# scout_mk2.net
KiCad netlist of a schematic drawn in EAGLE
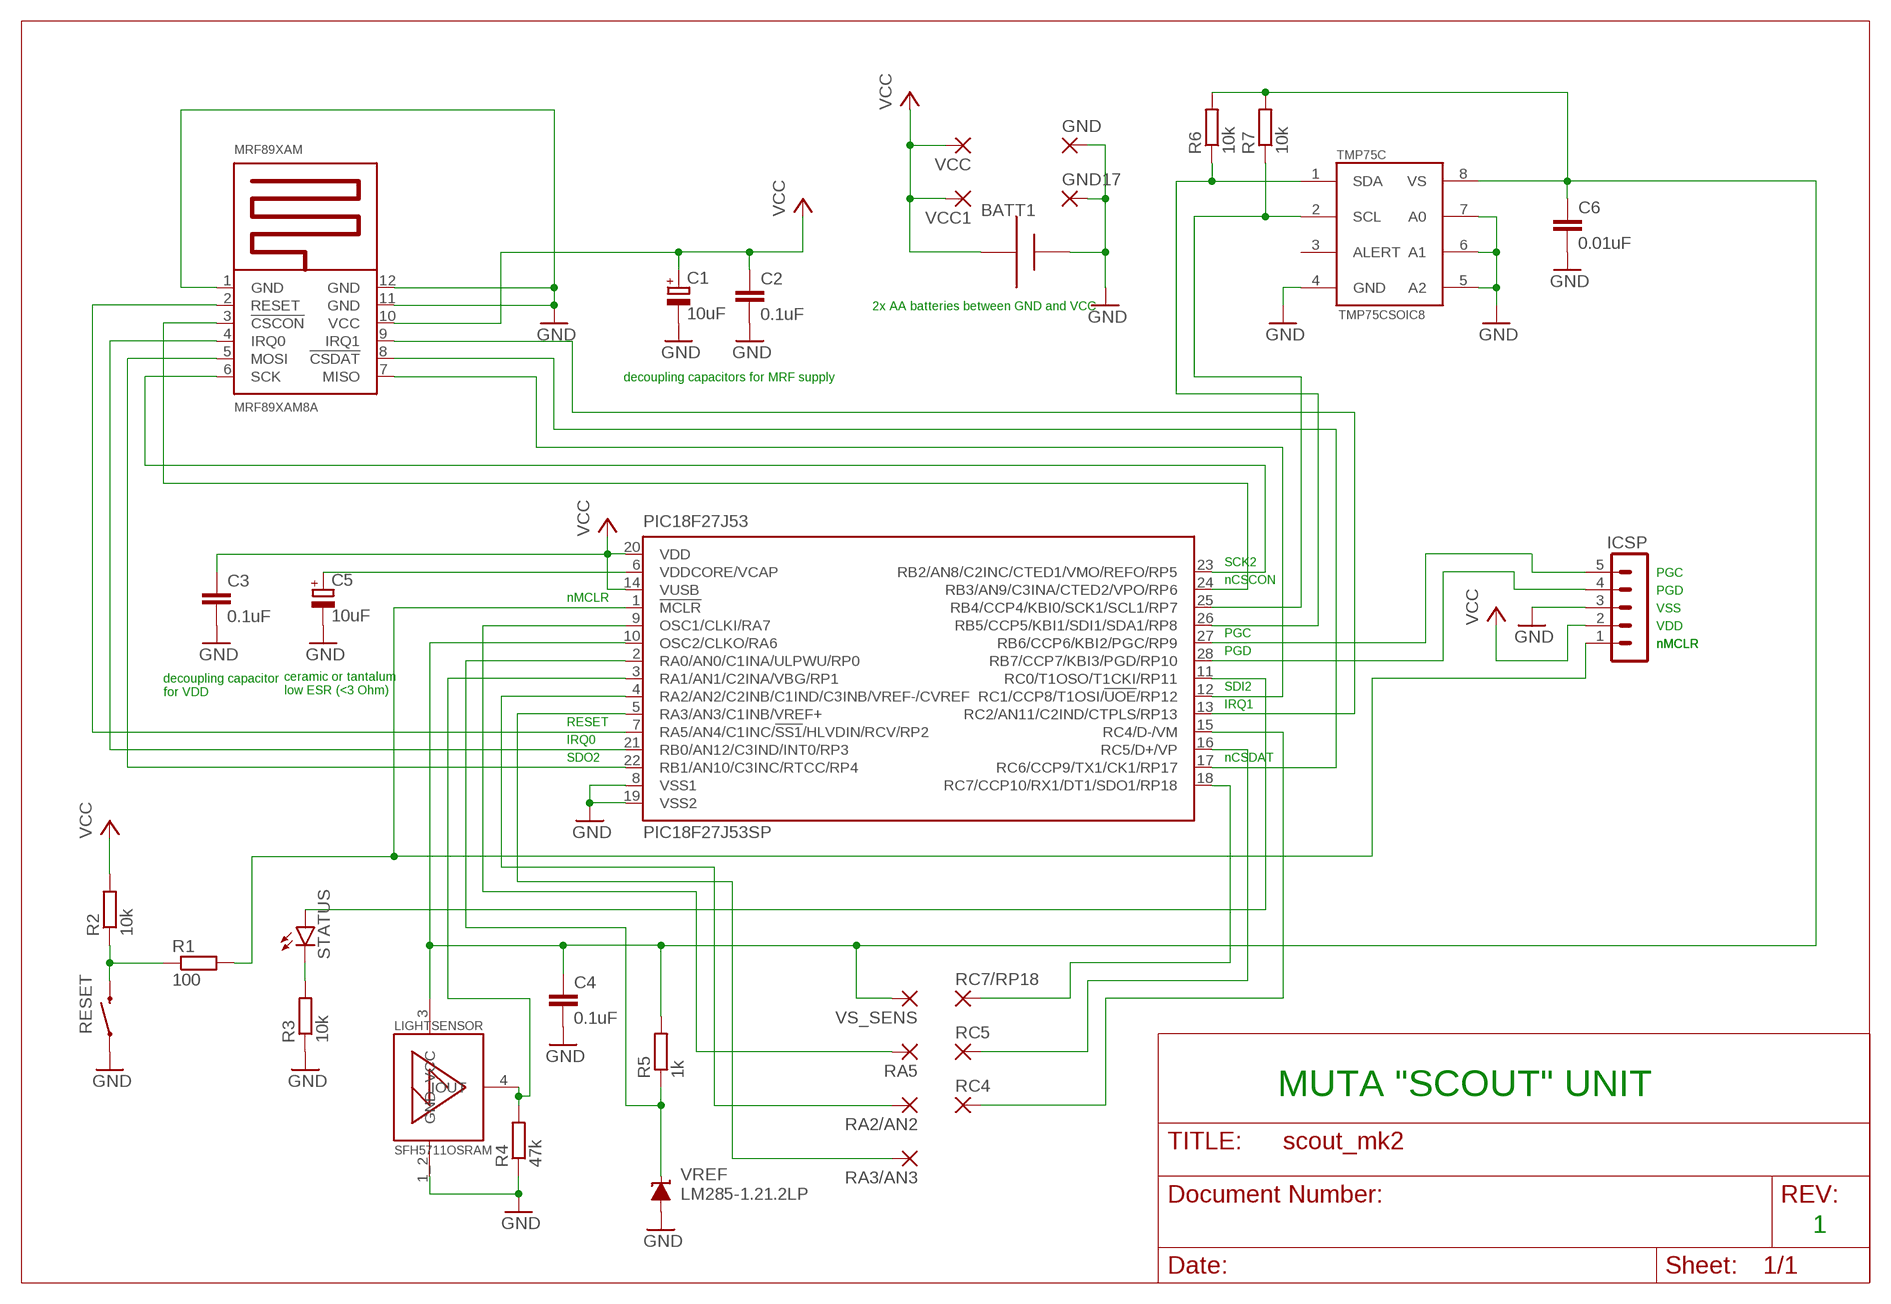
[diagram p0: schematic, sheet 1]

(export (version "E")
  (design (tool "Eeschema 10.0.6"))
  (components
    (comp (ref "BATT1")
      (value "AAA")
      (footprint "eagle-import:2XAAA")
      (libsource (lib "eagle-import") (part "AAA"))
    )
    (comp (ref "C1")
      (value "10uF")
      (footprint "eagle-import:TT5D6")
      (libsource (lib "eagle-import") (part "CPOL-EUTT6D6"))
    )
    (comp (ref "C2")
      (value "0.1uF")
      (footprint "eagle-import:C050-025X075")
      (libsource (lib "eagle-import") (part "C-EU050-025X075"))
    )
    (comp (ref "C3")
      (value "0.1uF")
      (footprint "eagle-import:C050-025X075")
      (libsource (lib "eagle-import") (part "C-EU050-025X075"))
    )
    (comp (ref "C4")
      (value "0.1uF")
      (footprint "eagle-import:C050-025X075")
      (libsource (lib "eagle-import") (part "C-EU050-025X075"))
    )
    (comp (ref "C5")
      (value "10uF")
      (footprint "eagle-import:C_6032-28R")
      (libsource (lib "eagle-import") (part "CPOL-EUC/6032-28R"))
    )
    (comp (ref "C6")
      (value "0.01uF")
      (footprint "eagle-import:C050-025X075")
      (libsource (lib "eagle-import") (part "C-EU050-025X075"))
    )
    (comp (ref "GND")
      (value "3,81/1,1")
      (footprint "eagle-import:3,81_1,1")
      (libsource (lib "eagle-import") (part "3,81/1,1"))
    )
    (comp (ref "GND17")
      (value "3,81/1,1")
      (footprint "eagle-import:3,81_1,1")
      (libsource (lib "eagle-import") (part "3,81/1,1"))
    )
    (comp (ref "ICSP")
      (value "MA05-1")
      (footprint "eagle-import:MA05-1")
      (libsource (lib "eagle-import") (part "MA05-1"))
    )
    (comp (ref "LIGHTSENSOR")
      (value "SFH5711OSRAM")
      (footprint "eagle-import:SFH5711")
      (libsource (lib "eagle-import") (part "SFH5711OSRAM"))
    )
    (comp (ref "MRF89XAM")
      (value "MRF89XAM8A")
      (footprint "eagle-import:MRF89XAMXA")
      (libsource (lib "eagle-import") (part "MRF89XAM8A"))
    )
    (comp (ref "PIC18F27J53")
      (value "PIC18F27J53SP")
      (footprint "eagle-import:DIL28-3")
      (fields (field (name "MPN") "PIC18F27J53-I/SP"))
      (libsource (lib "eagle-import") (part "PIC18F2J53SP7"))
    )
    (comp (ref "R1")
      (value "100")
      (footprint "eagle-import:0207_10")
      (libsource (lib "eagle-import") (part "R-EU_0207_10"))
    )
    (comp (ref "R2")
      (value "10k")
      (footprint "eagle-import:0207_10")
      (libsource (lib "eagle-import") (part "R-EU_0207_10"))
    )
    (comp (ref "R3")
      (value "10k")
      (footprint "eagle-import:0207_2V")
      (libsource (lib "eagle-import") (part "R-EU_0207_2V"))
    )
    (comp (ref "R4")
      (value "47k")
      (footprint "eagle-import:0207_10")
      (libsource (lib "eagle-import") (part "R-EU_0207_10"))
    )
    (comp (ref "R5")
      (value "1k")
      (footprint "eagle-import:0207_10")
      (libsource (lib "eagle-import") (part "R-EU_0207_10"))
    )
    (comp (ref "R6")
      (value "10k")
      (footprint "eagle-import:0207_10")
      (libsource (lib "eagle-import") (part "R-EU_0207_10"))
    )
    (comp (ref "R7")
      (value "10k")
      (footprint "eagle-import:0207_10")
      (libsource (lib "eagle-import") (part "R-EU_0207_10"))
    )
    (comp (ref "RA2/AN2")
      (value "3,81/1,1")
      (footprint "eagle-import:3,81_1,1")
      (libsource (lib "eagle-import") (part "3,81/1,1"))
    )
    (comp (ref "RA3/AN3")
      (value "3,81/1,1")
      (footprint "eagle-import:3,81_1,1")
      (libsource (lib "eagle-import") (part "3,81/1,1"))
    )
    (comp (ref "RA5")
      (value "3,81/1,1")
      (footprint "eagle-import:3,81_1,1")
      (libsource (lib "eagle-import") (part "3,81/1,1"))
    )
    (comp (ref "RC4")
      (value "3,81/1,1")
      (footprint "eagle-import:3,81_1,1")
      (libsource (lib "eagle-import") (part "3,81/1,1"))
    )
    (comp (ref "RC5")
      (value "3,81/1,1")
      (footprint "eagle-import:3,81_1,1")
      (libsource (lib "eagle-import") (part "3,81/1,1"))
    )
    (comp (ref "RC7/RP18")
      (value "3,81/1,1")
      (footprint "eagle-import:3,81_1,1")
      (libsource (lib "eagle-import") (part "3,81/1,1"))
    )
    (comp (ref "RESET")
      (value "SWITCH-MOMENTARY-2PTH")
      (footprint "eagle-import:TACTILE-PTH")
      (libsource (lib "eagle-import") (part "SWITCH-MOMENTARY-2PTH"))
    )
    (comp (ref "STATUS")
      (value "LED1206")
      (footprint "eagle-import:LED-1206")
      (libsource (lib "eagle-import") (part "LED1206"))
    )
    (comp (ref "TMP75C")
      (value "TMP75CSOIC8")
      (footprint "eagle-import:SOIC8")
      (libsource (lib "eagle-import") (part "TMP75CSOIC8"))
    )
    (comp (ref "VCC")
      (value "3,81/1,1")
      (footprint "eagle-import:3,81_1,1")
      (libsource (lib "eagle-import") (part "3,81/1,1"))
    )
    (comp (ref "VCC1")
      (value "3,81/1,1")
      (footprint "eagle-import:3,81_1,1")
      (libsource (lib "eagle-import") (part "3,81/1,1"))
    )
    (comp (ref "VREF")
      (value "LM285-1.21.2LP")
      (footprint "eagle-import:LP_O-PBCY-W3")
      (libsource (lib "eagle-import") (part "LM285-1.21.2LP"))
    )
    (comp (ref "VS_SENS")
      (value "3,81/1,1")
      (footprint "eagle-import:3,81_1,1")
      (libsource (lib "eagle-import") (part "3,81/1,1"))
    )
  )
  (nets
    (net (code "1") (name "GND") (class "Default")
      (node (ref "BATT1") (pin "P$1") (pinfunction "+_P$1") (pintype "bidirectional"))
      (node (ref "C1") (pin "-") (pinfunction "-_-") (pintype "passive"))
      (node (ref "C2") (pin "2") (pinfunction "2_2") (pintype "passive"))
      (node (ref "C3") (pin "2") (pinfunction "2_2") (pintype "passive"))
      (node (ref "C4") (pin "2") (pinfunction "2_2") (pintype "passive"))
      (node (ref "C5") (pin "-") (pinfunction "-_-") (pintype "passive"))
      (node (ref "C6") (pin "2") (pinfunction "2_2") (pintype "passive"))
      (node (ref "GND") (pin "1") (pinfunction "P_1") (pintype "passive"))
      (node (ref "GND17") (pin "1") (pinfunction "P_1") (pintype "passive"))
      (node (ref "ICSP") (pin "3") (pinfunction "3_3") (pintype "passive"))
      (node (ref "LIGHTSENSOR") (pin "1_2") (pinfunction "GND_1_2") (pintype "bidirectional"))
      (node (ref "MRF89XAM") (pin "1") (pinfunction "GND_1") (pintype "power_in"))
      (node (ref "MRF89XAM") (pin "11") (pinfunction "GND_11") (pintype "power_in"))
      (node (ref "MRF89XAM") (pin "12") (pinfunction "GND_12") (pintype "power_in"))
      (node (ref "PIC18F27J53") (pin "19") (pinfunction "VSS2_19") (pintype "input"))
      (node (ref "PIC18F27J53") (pin "8") (pinfunction "VSS1_8") (pintype "input"))
      (node (ref "R3") (pin "1") (pinfunction "1_1") (pintype "passive"))
      (node (ref "R4") (pin "1") (pinfunction "1_1") (pintype "passive"))
      (node (ref "RESET") (pin "1") (pinfunction "1_1") (pintype "passive"))
      (node (ref "TMP75C") (pin "4") (pinfunction "GND_4") (pintype "bidirectional"))
      (node (ref "TMP75C") (pin "5") (pinfunction "A2_5") (pintype "bidirectional"))
      (node (ref "TMP75C") (pin "6") (pinfunction "A1_6") (pintype "bidirectional"))
      (node (ref "TMP75C") (pin "7") (pinfunction "A0_7") (pintype "bidirectional"))
      (node (ref "VREF") (pin "3") (pinfunction "A_3") (pintype "passive"))
    )
    (net (code "2") (name "Net-(LIGHTSENSOR-IOUT)") (class "Default")
      (node (ref "LIGHTSENSOR") (pin "4") (pinfunction "IOUT_4") (pintype "bidirectional"))
      (node (ref "PIC18F27J53") (pin "3") (pinfunction "RA1/AN1/C2INA/VBG/RP1_3") (pintype "bidirectional"))
      (node (ref "R4") (pin "2") (pinfunction "2_2") (pintype "passive"))
    )
    (net (code "3") (name "Net-(LIGHTSENSOR-VCC)") (class "Default")
      (node (ref "C4") (pin "1") (pinfunction "1_1") (pintype "passive"))
      (node (ref "C6") (pin "1") (pinfunction "1_1") (pintype "passive"))
      (node (ref "LIGHTSENSOR") (pin "3") (pinfunction "VCC_3") (pintype "bidirectional"))
      (node (ref "PIC18F27J53") (pin "10") (pinfunction "OSC2/CLKO/RA6_10") (pintype "bidirectional"))
      (node (ref "R5") (pin "2") (pinfunction "2_2") (pintype "passive"))
      (node (ref "R6") (pin "2") (pinfunction "2_2") (pintype "passive"))
      (node (ref "R7") (pin "2") (pinfunction "2_2") (pintype "passive"))
      (node (ref "TMP75C") (pin "8") (pinfunction "VS_8") (pintype "bidirectional"))
      (node (ref "VS_SENS") (pin "1") (pinfunction "P_1") (pintype "passive"))
    )
    (net (code "4") (name "Net-(MRF89XAM-IRQ0)") (class "Default")
      (node (ref "MRF89XAM") (pin "4") (pinfunction "IRQ0_4") (pintype "output"))
      (node (ref "PIC18F27J53") (pin "21") (pinfunction "RB0/AN12/C3IND/INT0/RP3_21") (pintype "bidirectional"))
    )
    (net (code "5") (name "Net-(MRF89XAM-IRQ1)") (class "Default")
      (node (ref "MRF89XAM") (pin "9") (pinfunction "IRQ1_9") (pintype "output"))
      (node (ref "PIC18F27J53") (pin "13") (pinfunction "RC2/AN11/C2IND/CTPLS/RP13_13") (pintype "bidirectional"))
    )
    (net (code "6") (name "Net-(MRF89XAM-MISO)") (class "Default")
      (node (ref "MRF89XAM") (pin "7") (pinfunction "MISO_7") (pintype "output"))
      (node (ref "PIC18F27J53") (pin "12") (pinfunction "RC1/CCP8/T1OSI/~{UOE}/RP12_12") (pintype "bidirectional"))
    )
    (net (code "7") (name "Net-(MRF89XAM-MOSI)") (class "Default")
      (node (ref "MRF89XAM") (pin "5") (pinfunction "MOSI_5") (pintype "input"))
      (node (ref "PIC18F27J53") (pin "22") (pinfunction "RB1/AN10/C3INC/RTCC/RP4_22") (pintype "bidirectional"))
    )
    (net (code "8") (name "Net-(MRF89XAM-RESET)") (class "Default")
      (node (ref "MRF89XAM") (pin "2") (pinfunction "RESET_2") (pintype "input"))
      (node (ref "PIC18F27J53") (pin "7") (pinfunction "RA5/AN4/C1INC/~{SS1}/HLVDIN/RCV/RP2_7") (pintype "bidirectional"))
    )
    (net (code "9") (name "Net-(MRF89XAM-SCK)") (class "Default")
      (node (ref "MRF89XAM") (pin "6") (pinfunction "SCK_6") (pintype "input"))
      (node (ref "PIC18F27J53") (pin "23") (pinfunction "RB2/AN8/C2INC/CTED1/VMO/REFO/RP5_23") (pintype "bidirectional"))
    )
    (net (code "10") (name "Net-(MRF89XAM-~{CSCON})") (class "Default")
      (node (ref "MRF89XAM") (pin "3") (pinfunction "~{CSCON}_3") (pintype "input"))
      (node (ref "PIC18F27J53") (pin "24") (pinfunction "RB3/AN9/C3INA/CTED2/VPO/RP6_24") (pintype "bidirectional"))
    )
    (net (code "11") (name "Net-(MRF89XAM-~{CSDAT})") (class "Default")
      (node (ref "MRF89XAM") (pin "8") (pinfunction "~{CSDAT}_8") (pintype "input"))
      (node (ref "PIC18F27J53") (pin "17") (pinfunction "RC6/CCP9/TX1/CK1/RP17_17") (pintype "bidirectional"))
    )
    (net (code "12") (name "Net-(PIC18F27J53-OSC1{slash}CLKI{slash}RA7)") (class "Default")
      (node (ref "PIC18F27J53") (pin "9") (pinfunction "OSC1/CLKI/RA7_9") (pintype "bidirectional"))
      (node (ref "RA5") (pin "1") (pinfunction "P_1") (pintype "passive"))
    )
    (net (code "13") (name "Net-(PIC18F27J53-RA0{slash}AN0{slash}C1INA{slash}ULPWU{slash}RP0)") (class "Default")
      (node (ref "PIC18F27J53") (pin "2") (pinfunction "RA0/AN0/C1INA/ULPWU/RP0_2") (pintype "bidirectional"))
      (node (ref "R5") (pin "1") (pinfunction "1_1") (pintype "passive"))
      (node (ref "VREF") (pin "2") (pinfunction "C_2") (pintype "passive"))
    )
    (net (code "14") (name "Net-(PIC18F27J53-RA2{slash}AN2{slash}C2INB{slash}C1IND{slash}C3INB{slash}VREF-{slash}CVREF)") (class "Default")
      (node (ref "PIC18F27J53") (pin "4") (pinfunction "RA2/AN2/C2INB/C1IND/C3INB/VREF-/CVREF_4") (pintype "bidirectional"))
      (node (ref "RA2/AN2") (pin "1") (pinfunction "P_1") (pintype "passive"))
    )
    (net (code "15") (name "Net-(PIC18F27J53-RA3{slash}AN3{slash}C1INB{slash}VREF+)") (class "Default")
      (node (ref "PIC18F27J53") (pin "5") (pinfunction "RA3/AN3/C1INB/VREF+_5") (pintype "bidirectional"))
      (node (ref "RA3/AN3") (pin "1") (pinfunction "P_1") (pintype "passive"))
    )
    (net (code "16") (name "Net-(PIC18F27J53-RB4{slash}CCP4{slash}KBI0{slash}SCK1{slash}SCL1{slash}RP7)") (class "Default")
      (node (ref "PIC18F27J53") (pin "25") (pinfunction "RB4/CCP4/KBI0/SCK1/SCL1/RP7_25") (pintype "bidirectional"))
      (node (ref "R7") (pin "1") (pinfunction "1_1") (pintype "passive"))
      (node (ref "TMP75C") (pin "2") (pinfunction "SCL_2") (pintype "bidirectional"))
    )
    (net (code "17") (name "Net-(PIC18F27J53-RB5{slash}CCP5{slash}KBI1{slash}SDI1{slash}SDA1{slash}RP8)") (class "Default")
      (node (ref "PIC18F27J53") (pin "26") (pinfunction "RB5/CCP5/KBI1/SDI1/SDA1/RP8_26") (pintype "bidirectional"))
      (node (ref "R6") (pin "1") (pinfunction "1_1") (pintype "passive"))
      (node (ref "TMP75C") (pin "1") (pinfunction "SDA_1") (pintype "bidirectional"))
    )
    (net (code "18") (name "Net-(PIC18F27J53-RB6{slash}CCP6{slash}KBI2{slash}PGC{slash}RP9)") (class "Default")
      (node (ref "ICSP") (pin "5") (pinfunction "5_5") (pintype "passive"))
      (node (ref "PIC18F27J53") (pin "27") (pinfunction "RB6/CCP6/KBI2/PGC/RP9_27") (pintype "bidirectional"))
    )
    (net (code "19") (name "Net-(PIC18F27J53-RB7{slash}CCP7{slash}KBI3{slash}PGD{slash}RP10)") (class "Default")
      (node (ref "ICSP") (pin "4") (pinfunction "4_4") (pintype "passive"))
      (node (ref "PIC18F27J53") (pin "28") (pinfunction "RB7/CCP7/KBI3/PGD/RP10_28") (pintype "bidirectional"))
    )
    (net (code "20") (name "Net-(PIC18F27J53-RC0{slash}T1OSO{slash}T1CKI{slash}RP11)") (class "Default")
      (node (ref "PIC18F27J53") (pin "11") (pinfunction "RC0/T1OSO/T1CKI/RP11_11") (pintype "bidirectional"))
      (node (ref "STATUS") (pin "A") (pinfunction "A_A") (pintype "passive"))
    )
    (net (code "21") (name "Net-(PIC18F27J53-RC4{slash}D-{slash}VM)") (class "Default")
      (node (ref "PIC18F27J53") (pin "15") (pinfunction "RC4/D-/VM_15") (pintype "bidirectional"))
      (node (ref "RC4") (pin "1") (pinfunction "P_1") (pintype "passive"))
    )
    (net (code "22") (name "Net-(PIC18F27J53-RC5{slash}D+{slash}VP)") (class "Default")
      (node (ref "PIC18F27J53") (pin "16") (pinfunction "RC5/D+/VP_16") (pintype "bidirectional"))
      (node (ref "RC5") (pin "1") (pinfunction "P_1") (pintype "passive"))
    )
    (net (code "23") (name "Net-(PIC18F27J53-RC7{slash}CCP10{slash}RX1{slash}DT1{slash}SDO1{slash}RP18)") (class "Default")
      (node (ref "PIC18F27J53") (pin "18") (pinfunction "RC7/CCP10/RX1/DT1/SDO1/RP18_18") (pintype "bidirectional"))
      (node (ref "RC7/RP18") (pin "1") (pinfunction "P_1") (pintype "passive"))
    )
    (net (code "24") (name "Net-(PIC18F27J53-VDDCORE{slash}VCAP)") (class "Default")
      (node (ref "C5") (pin "+") (pinfunction "+_+") (pintype "passive"))
      (node (ref "PIC18F27J53") (pin "6") (pinfunction "VDDCORE/VCAP_6") (pintype "input"))
    )
    (net (code "25") (name "Net-(PIC18F27J53-~{MCLR})") (class "Default")
      (node (ref "ICSP") (pin "1") (pinfunction "1_1") (pintype "passive"))
      (node (ref "PIC18F27J53") (pin "1") (pinfunction "~{MCLR}_1") (pintype "input"))
      (node (ref "R1") (pin "2") (pinfunction "2_2") (pintype "passive"))
    )
    (net (code "26") (name "Net-(R3-Pad2)") (class "Default")
      (node (ref "R3") (pin "2") (pinfunction "2_2") (pintype "passive"))
      (node (ref "STATUS") (pin "C") (pinfunction "C_C") (pintype "passive"))
    )
    (net (code "27") (name "Net-(RESET-2)") (class "Default")
      (node (ref "R1") (pin "1") (pinfunction "1_1") (pintype "passive"))
      (node (ref "R2") (pin "1") (pinfunction "1_1") (pintype "passive"))
      (node (ref "RESET") (pin "3") (pinfunction "2_3") (pintype "passive"))
    )
    (net (code "28") (name "VCC") (class "Default")
      (node (ref "BATT1") (pin "P$2") (pinfunction "-_P$2") (pintype "bidirectional"))
      (node (ref "C1") (pin "+") (pinfunction "+_+") (pintype "passive"))
      (node (ref "C2") (pin "1") (pinfunction "1_1") (pintype "passive"))
      (node (ref "C3") (pin "1") (pinfunction "1_1") (pintype "passive"))
      (node (ref "ICSP") (pin "2") (pinfunction "2_2") (pintype "passive"))
      (node (ref "MRF89XAM") (pin "10") (pinfunction "VCC_10") (pintype "power_in"))
      (node (ref "PIC18F27J53") (pin "14") (pinfunction "VUSB_14") (pintype "input"))
      (node (ref "PIC18F27J53") (pin "20") (pinfunction "VDD_20") (pintype "input"))
      (node (ref "R2") (pin "2") (pinfunction "2_2") (pintype "passive"))
      (node (ref "VCC") (pin "1") (pinfunction "P_1") (pintype "passive"))
      (node (ref "VCC1") (pin "1") (pinfunction "P_1") (pintype "passive"))
    )
    (net (code "29") (name "unconnected-(TMP75C-ALERT-Pad3)") (class "Default")
      (node (ref "TMP75C") (pin "3") (pinfunction "ALERT_3") (pintype "bidirectional"))
    )
  )
)
